# plp-ctop_3a.net
KiCad netlist of a schematic drawn in Altium Designer
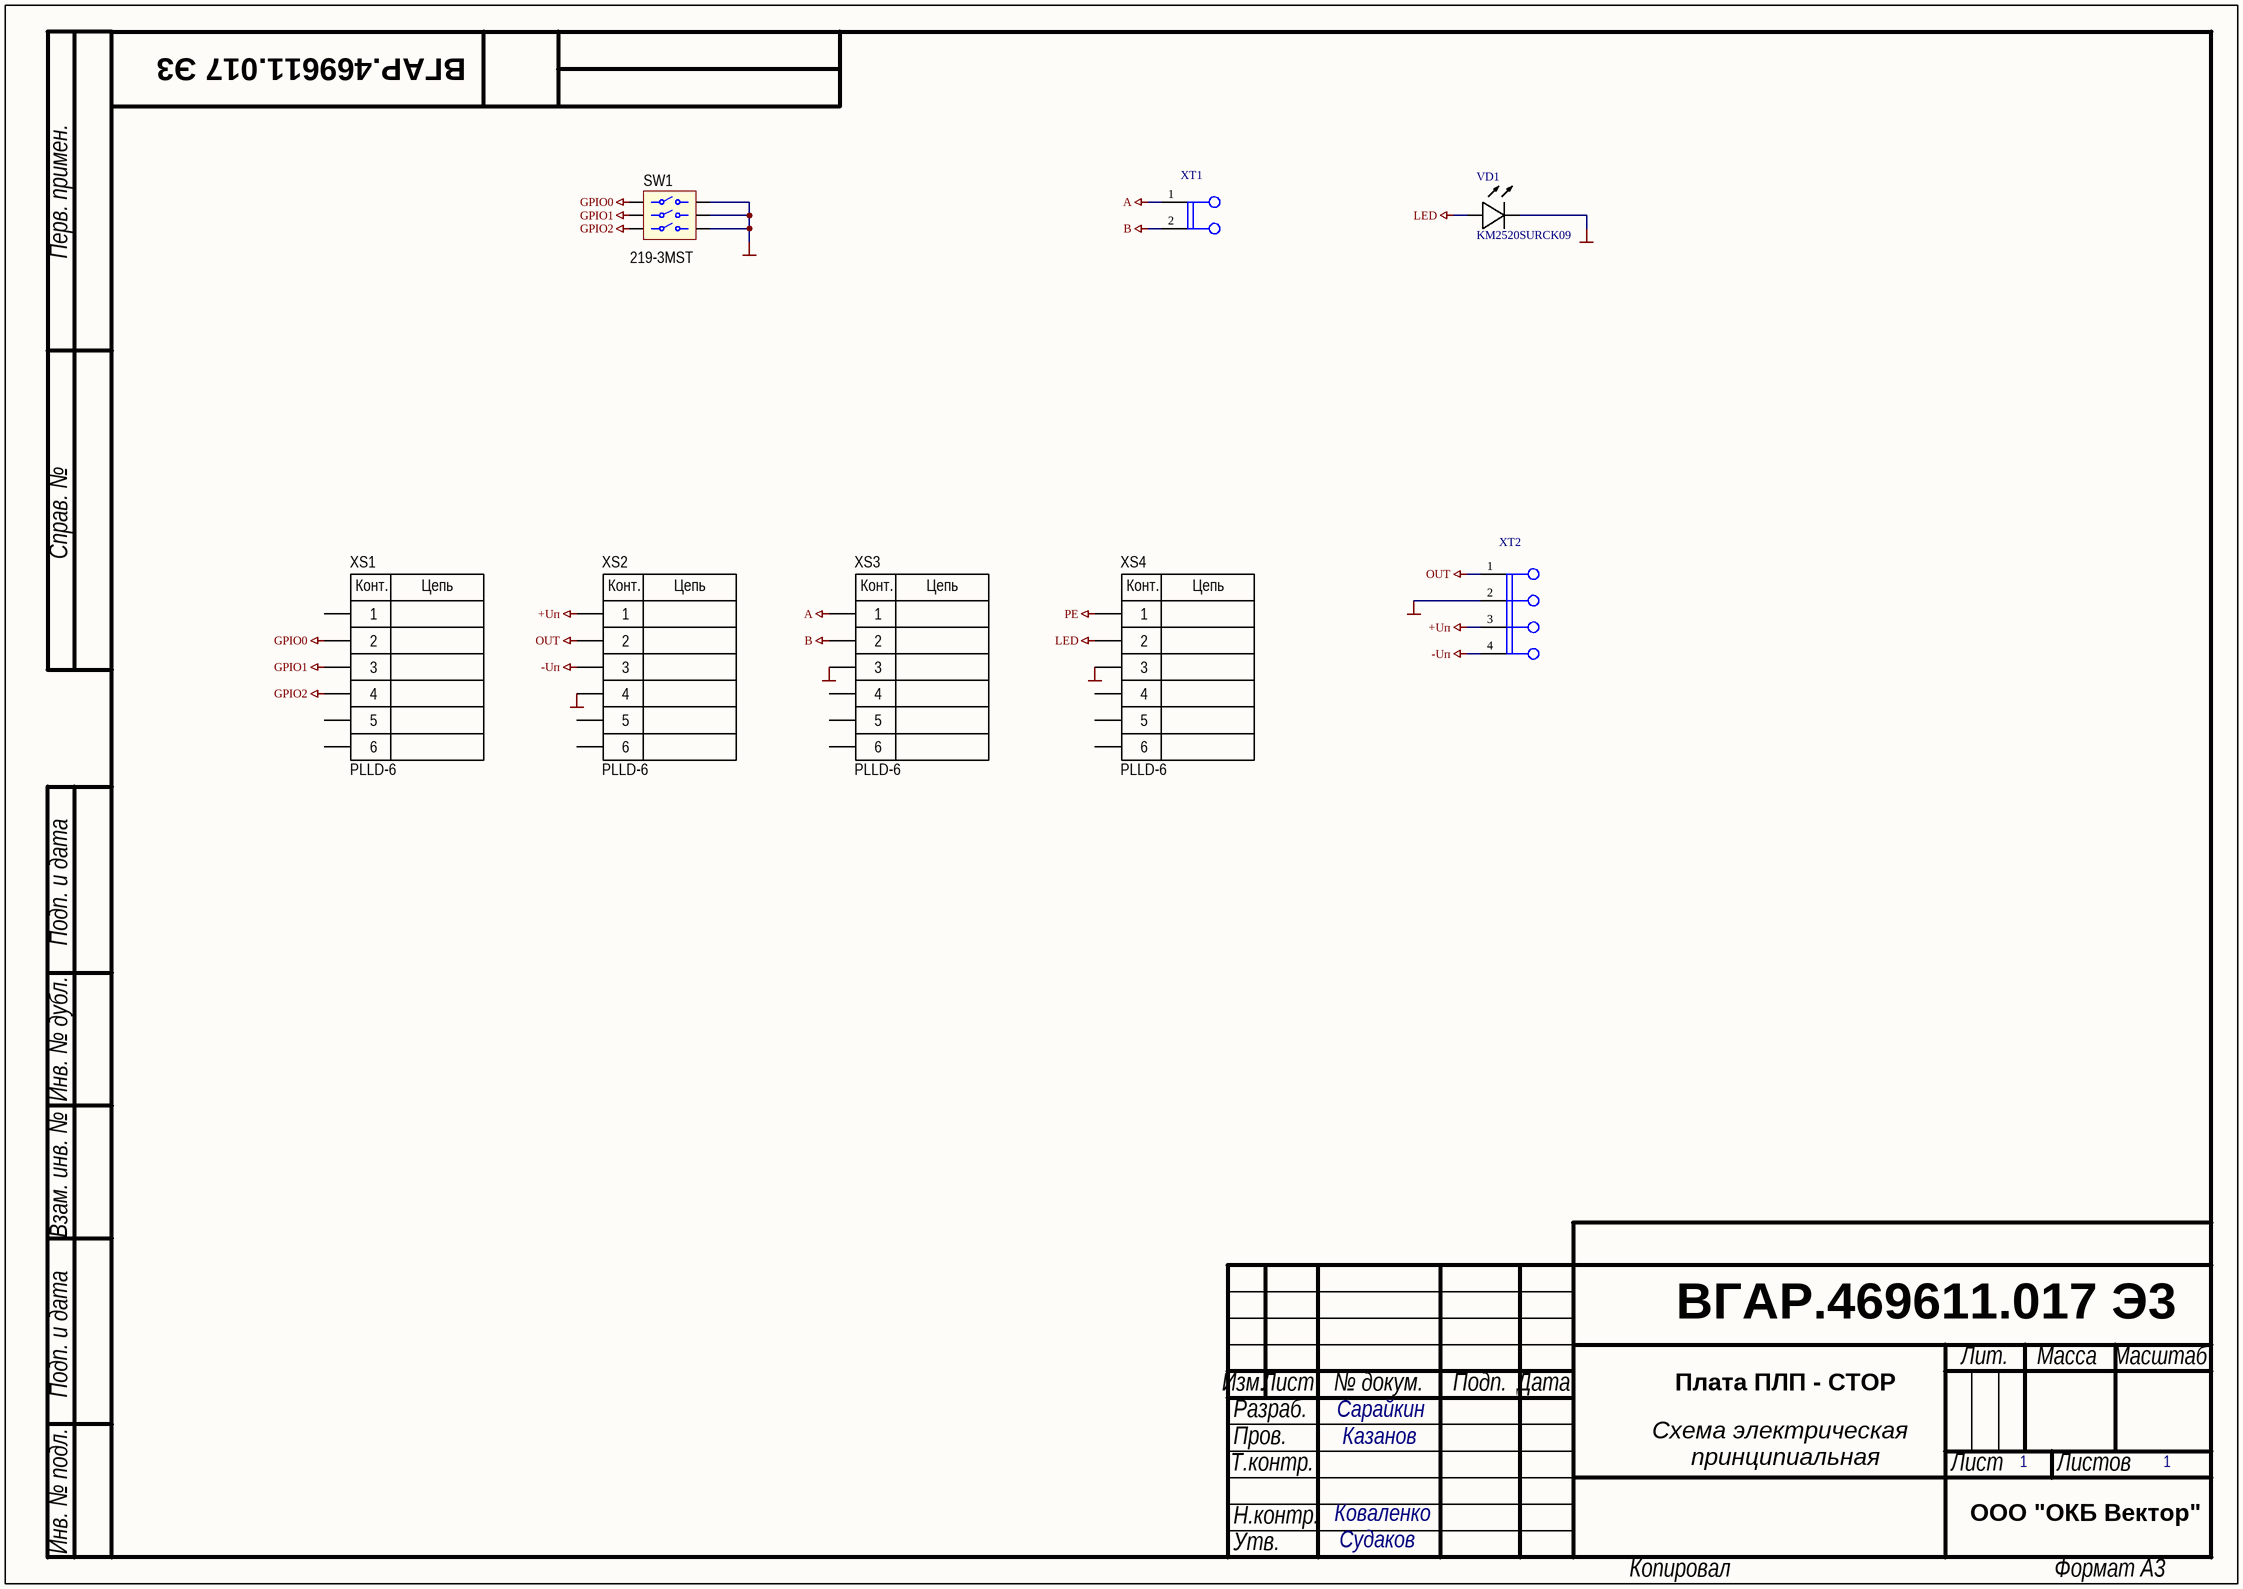
[diagram p0: plp-ctop_3a.SchDoc]

(export (version "E")
  (design (tool "Eeschema 10.0.6"))
  (components
    (comp (ref "SW1")
      (value "219-3MST")
      (footprint "219-3MST")
      (libsource (lib "electromechanics") (part "219-3MST"))
    )
    (comp (ref "VD1")
      (value "KM2520SURCK09")
      (footprint "KM2520SURCK09")
      (description "LED")
      (libsource (lib "Kingbright LED") (part "KM2520SURCK09"))
    )
    (comp (ref "XS1")
      (value "PLLD-6")
      (footprint "CON: PLL-6(2x3R1.27female)")
      (description "Step 1.27")
      (libsource (lib "connector") (part "PLLD-6(Female)"))
    )
    (comp (ref "XS2")
      (value "PLLD-6")
      (footprint "CON: PLL-6(2x3R1.27female)")
      (description "Step 1.27")
      (libsource (lib "connector") (part "PLLD-6(Female)"))
    )
    (comp (ref "XS3")
      (value "PLLD-6")
      (footprint "CON: PLL-6(2x3R1.27female)")
      (description "Step 1.27")
      (libsource (lib "connector") (part "PLLD-6(Female)"))
    )
    (comp (ref "XS4")
      (value "PLLD-6")
      (footprint "CON: PLL-6(2x3R1.27female)")
      (description "Step 1.27")
      (libsource (lib "connector") (part "PLLD-6(Female)"))
    )
    (comp (ref "XT1")
      (value "MKDS 1/2 - 3,5")
      (footprint "MKDS 1/2 - 3,5")
      (description "Клемник")
      (fields (field (name "MANUFACTURER") "Poenix Contact"))
      (libsource (lib "Phoenixcontact Terminal Block") (part "MKDS 1/2 - 3,5"))
    )
    (comp (ref "XT2")
      (value "MKDS 1/4 - 3,5")
      (footprint "MKDS 1/4 - 3,5")
      (description "Клемник")
      (fields (field (name "MANUFACTURER") "Poenix Contact"))
      (libsource (lib "Phoenixcontact Terminal Block") (part "MKDS 1/4 - 3,5"))
    )
  )
  (nets
    (net (code "1") (name "+Uп") (class "Default")
      (node (ref "XS2") (pin "1") (pinfunction "1_1") (pintype "passive"))
      (node (ref "XT2") (pin "3") (pinfunction "3_3") (pintype "passive"))
    )
    (net (code "2") (name "-Uп") (class "Default")
      (node (ref "XS2") (pin "3") (pinfunction "3_3") (pintype "passive"))
      (node (ref "XT2") (pin "4") (pinfunction "4_4") (pintype "passive"))
    )
    (net (code "3") (name "A") (class "Default")
      (node (ref "XS3") (pin "1") (pinfunction "1_1") (pintype "passive"))
      (node (ref "XT1") (pin "1") (pinfunction "1_1") (pintype "passive"))
    )
    (net (code "4") (name "B") (class "Default")
      (node (ref "XS3") (pin "2") (pinfunction "2_2") (pintype "passive"))
      (node (ref "XT1") (pin "2") (pinfunction "2_2") (pintype "passive"))
    )
    (net (code "5") (name "GND") (class "Default")
      (node (ref "SW1") (pin "4") (pinfunction "4_4") (pintype "passive"))
      (node (ref "SW1") (pin "5") (pinfunction "5_5") (pintype "passive"))
      (node (ref "SW1") (pin "6") (pinfunction "6_6") (pintype "passive"))
      (node (ref "VD1") (pin "2") (pinfunction "K_2") (pintype "passive"))
      (node (ref "XS2") (pin "4") (pinfunction "4_4") (pintype "passive"))
      (node (ref "XS3") (pin "3") (pinfunction "3_3") (pintype "passive"))
      (node (ref "XS4") (pin "3") (pinfunction "3_3") (pintype "passive"))
      (node (ref "XT2") (pin "2") (pinfunction "2_2") (pintype "passive"))
    )
    (net (code "6") (name "GPIO0") (class "Default")
      (node (ref "SW1") (pin "1") (pinfunction "1_1") (pintype "passive"))
      (node (ref "XS1") (pin "2") (pinfunction "2_2") (pintype "passive"))
    )
    (net (code "7") (name "GPIO1") (class "Default")
      (node (ref "SW1") (pin "2") (pinfunction "2_2") (pintype "passive"))
      (node (ref "XS1") (pin "3") (pinfunction "3_3") (pintype "passive"))
    )
    (net (code "8") (name "GPIO2") (class "Default")
      (node (ref "SW1") (pin "3") (pinfunction "3_3") (pintype "passive"))
      (node (ref "XS1") (pin "4") (pinfunction "4_4") (pintype "passive"))
    )
    (net (code "9") (name "LED") (class "Default")
      (node (ref "VD1") (pin "1") (pinfunction "A_1") (pintype "passive"))
      (node (ref "XS4") (pin "2") (pinfunction "2_2") (pintype "passive"))
    )
    (net (code "10") (name "OUT") (class "Default")
      (node (ref "XS2") (pin "2") (pinfunction "2_2") (pintype "passive"))
      (node (ref "XT2") (pin "1") (pinfunction "1_1") (pintype "passive"))
    )
    (net (code "11") (name "PE") (class "Default")
      (node (ref "XS4") (pin "1") (pinfunction "1_1") (pintype "passive"))
    )
    (net (code "12") (name "unconnected-(XS1-Pad1)") (class "Default")
      (node (ref "XS1") (pin "1") (pinfunction "1_1") (pintype "passive"))
    )
    (net (code "13") (name "unconnected-(XS1-Pad5)") (class "Default")
      (node (ref "XS1") (pin "5") (pinfunction "5_5") (pintype "passive"))
    )
    (net (code "14") (name "unconnected-(XS1-Pad6)") (class "Default")
      (node (ref "XS1") (pin "6") (pinfunction "6_6") (pintype "passive"))
    )
    (net (code "15") (name "unconnected-(XS2-Pad5)") (class "Default")
      (node (ref "XS2") (pin "5") (pinfunction "5_5") (pintype "passive"))
    )
    (net (code "16") (name "unconnected-(XS2-Pad6)") (class "Default")
      (node (ref "XS2") (pin "6") (pinfunction "6_6") (pintype "passive"))
    )
    (net (code "17") (name "unconnected-(XS3-Pad4)") (class "Default")
      (node (ref "XS3") (pin "4") (pinfunction "4_4") (pintype "passive"))
    )
    (net (code "18") (name "unconnected-(XS3-Pad5)") (class "Default")
      (node (ref "XS3") (pin "5") (pinfunction "5_5") (pintype "passive"))
    )
    (net (code "19") (name "unconnected-(XS3-Pad6)") (class "Default")
      (node (ref "XS3") (pin "6") (pinfunction "6_6") (pintype "passive"))
    )
    (net (code "20") (name "unconnected-(XS4-Pad4)") (class "Default")
      (node (ref "XS4") (pin "4") (pinfunction "4_4") (pintype "passive"))
    )
    (net (code "21") (name "unconnected-(XS4-Pad5)") (class "Default")
      (node (ref "XS4") (pin "5") (pinfunction "5_5") (pintype "passive"))
    )
    (net (code "22") (name "unconnected-(XS4-Pad6)") (class "Default")
      (node (ref "XS4") (pin "6") (pinfunction "6_6") (pintype "passive"))
    )
  )
)
